# v1.net
KiCad netlist of a schematic drawn in EAGLE
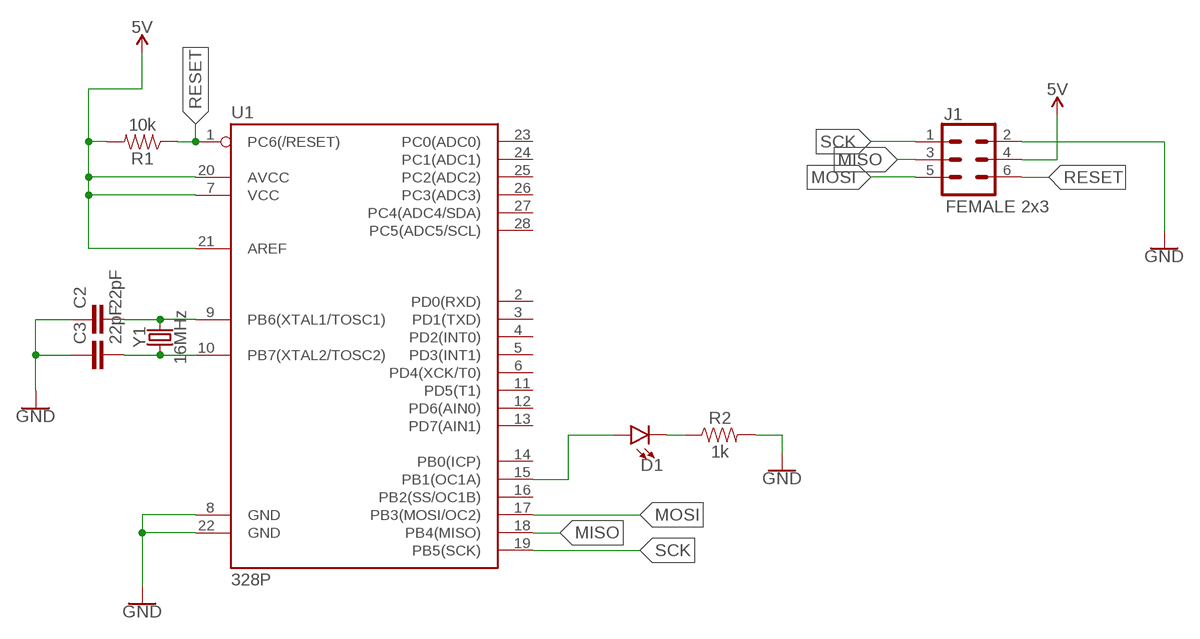
[diagram p0: schematic, sheet 1]

(export (version "E")
  (design (tool "Eeschema 10.0.6"))
  (components
    (comp (ref "C2")
      (value "22pF")
      (footprint "eagle-import:CAP-PTH-2.54")
      (libsource (lib "eagle-import") (part "22PF-PTH-2.54MM-200V-5%"))
    )
    (comp (ref "C3")
      (value "22pF")
      (footprint "eagle-import:CAP-PTH-2.54")
      (libsource (lib "eagle-import") (part "22PF-PTH-2.54MM-200V-5%"))
    )
    (comp (ref "D1")
      (value "LED3MM")
      (footprint "eagle-import:LED_3MM")
      (libsource (lib "eagle-import") (part "LED3MM"))
    )
    (comp (ref "J1")
      (value "FEMALE 2x3")
      (footprint "eagle-import:2X3")
      (libsource (lib "eagle-import") (part "CONN_03X2FEMALE"))
    )
    (comp (ref "R1")
      (value "10k")
      (footprint "eagle-import:AXIAL-0.3")
      (libsource (lib "eagle-import") (part "1KOHM-HORIZ-1/4W-1%"))
    )
    (comp (ref "R2")
      (value "1k")
      (footprint "eagle-import:AXIAL-0.3")
      (libsource (lib "eagle-import") (part "1KOHM-HORIZ-1/4W-1%"))
    )
    (comp (ref "U1")
      (value "328P")
      (footprint "eagle-import:DIP28")
      (libsource (lib "eagle-import") (part "ATMEGA328P_PDIP"))
    )
    (comp (ref "Y1")
      (value "16MHz")
      (footprint "eagle-import:HC49US")
      (libsource (lib "eagle-import") (part "CRYSTAL-16MHZPTH-HC49US"))
    )
  )
  (nets
    (net (code "1") (name "5V") (class "Default")
      (node (ref "J1") (pin "4") (pinfunction "4_4") (pintype "bidirectional"))
      (node (ref "R1") (pin "P$2") (pinfunction "2_P$2") (pintype "passive"))
      (node (ref "U1") (pin "20") (pinfunction "AVCC_20") (pintype "bidirectional"))
      (node (ref "U1") (pin "21") (pinfunction "AREF_21") (pintype "bidirectional"))
      (node (ref "U1") (pin "7") (pinfunction "VCC_7") (pintype "bidirectional"))
    )
    (net (code "2") (name "GND") (class "Default")
      (node (ref "C2") (pin "1") (pinfunction "1_1") (pintype "passive"))
      (node (ref "C3") (pin "1") (pinfunction "1_1") (pintype "passive"))
      (node (ref "J1") (pin "2") (pinfunction "2_2") (pintype "bidirectional"))
      (node (ref "R2") (pin "P$2") (pinfunction "2_P$2") (pintype "passive"))
      (node (ref "U1") (pin "22") (pinfunction "GND_22") (pintype "bidirectional"))
      (node (ref "U1") (pin "8") (pinfunction "GND_8") (pintype "bidirectional"))
    )
    (net (code "3") (name "MISO") (class "Default")
      (node (ref "J1") (pin "3") (pinfunction "3_3") (pintype "bidirectional"))
      (node (ref "U1") (pin "18") (pinfunction "PB4(MISO)_18") (pintype "bidirectional"))
    )
    (net (code "4") (name "MOSI") (class "Default")
      (node (ref "J1") (pin "5") (pinfunction "5_5") (pintype "bidirectional"))
      (node (ref "U1") (pin "17") (pinfunction "PB3(MOSI/OC2)_17") (pintype "bidirectional"))
    )
    (net (code "5") (name "Net-(D1-C)") (class "Default")
      (node (ref "D1") (pin "K") (pinfunction "C_K") (pintype "passive"))
      (node (ref "R2") (pin "P$1") (pinfunction "1_P$1") (pintype "passive"))
    )
    (net (code "6") (name "Net-(U1-PB1(OC1A))") (class "Default")
      (node (ref "D1") (pin "A") (pinfunction "A_A") (pintype "passive"))
      (node (ref "U1") (pin "15") (pinfunction "PB1(OC1A)_15") (pintype "bidirectional"))
    )
    (net (code "7") (name "Net-(U1-PB6(XTAL1{slash}TOSC1))") (class "Default")
      (node (ref "C2") (pin "2") (pinfunction "2_2") (pintype "passive"))
      (node (ref "U1") (pin "9") (pinfunction "PB6(XTAL1/TOSC1)_9") (pintype "bidirectional"))
      (node (ref "Y1") (pin "2") (pinfunction "2_2") (pintype "passive"))
    )
    (net (code "8") (name "Net-(U1-PB7(XTAL2{slash}TOSC2))") (class "Default")
      (node (ref "C3") (pin "2") (pinfunction "2_2") (pintype "passive"))
      (node (ref "U1") (pin "10") (pinfunction "PB7(XTAL2/TOSC2)_10") (pintype "bidirectional"))
      (node (ref "Y1") (pin "1") (pinfunction "1_1") (pintype "passive"))
    )
    (net (code "9") (name "RESET") (class "Default")
      (node (ref "J1") (pin "6") (pinfunction "6_6") (pintype "bidirectional"))
      (node (ref "R1") (pin "P$1") (pinfunction "1_P$1") (pintype "passive"))
      (node (ref "U1") (pin "1") (pinfunction "PC6(/RESET)_1") (pintype "bidirectional"))
    )
    (net (code "10") (name "SCK") (class "Default")
      (node (ref "J1") (pin "1") (pinfunction "1_1") (pintype "bidirectional"))
      (node (ref "U1") (pin "19") (pinfunction "PB5(SCK)_19") (pintype "bidirectional"))
    )
    (net (code "11") (name "unconnected-(U1-PB0(ICP)-Pad14)") (class "Default")
      (node (ref "U1") (pin "14") (pinfunction "PB0(ICP)_14") (pintype "bidirectional"))
    )
    (net (code "12") (name "unconnected-(U1-PB2(SS{slash}OC1B)-Pad16)") (class "Default")
      (node (ref "U1") (pin "16") (pinfunction "PB2(SS/OC1B)_16") (pintype "bidirectional"))
    )
    (net (code "13") (name "unconnected-(U1-PC0(ADC0)-Pad23)") (class "Default")
      (node (ref "U1") (pin "23") (pinfunction "PC0(ADC0)_23") (pintype "bidirectional"))
    )
    (net (code "14") (name "unconnected-(U1-PC1(ADC1)-Pad24)") (class "Default")
      (node (ref "U1") (pin "24") (pinfunction "PC1(ADC1)_24") (pintype "bidirectional"))
    )
    (net (code "15") (name "unconnected-(U1-PC2(ADC2)-Pad25)") (class "Default")
      (node (ref "U1") (pin "25") (pinfunction "PC2(ADC2)_25") (pintype "bidirectional"))
    )
    (net (code "16") (name "unconnected-(U1-PC3(ADC3)-Pad26)") (class "Default")
      (node (ref "U1") (pin "26") (pinfunction "PC3(ADC3)_26") (pintype "bidirectional"))
    )
    (net (code "17") (name "unconnected-(U1-PC4(ADC4{slash}SDA)-Pad27)") (class "Default")
      (node (ref "U1") (pin "27") (pinfunction "PC4(ADC4/SDA)_27") (pintype "bidirectional"))
    )
    (net (code "18") (name "unconnected-(U1-PC5(ADC5{slash}SCL)-Pad28)") (class "Default")
      (node (ref "U1") (pin "28") (pinfunction "PC5(ADC5/SCL)_28") (pintype "bidirectional"))
    )
    (net (code "19") (name "unconnected-(U1-PD0(RXD)-Pad2)") (class "Default")
      (node (ref "U1") (pin "2") (pinfunction "PD0(RXD)_2") (pintype "bidirectional"))
    )
    (net (code "20") (name "unconnected-(U1-PD1(TXD)-Pad3)") (class "Default")
      (node (ref "U1") (pin "3") (pinfunction "PD1(TXD)_3") (pintype "bidirectional"))
    )
    (net (code "21") (name "unconnected-(U1-PD2(INT0)-Pad4)") (class "Default")
      (node (ref "U1") (pin "4") (pinfunction "PD2(INT0)_4") (pintype "bidirectional"))
    )
    (net (code "22") (name "unconnected-(U1-PD3(INT1)-Pad5)") (class "Default")
      (node (ref "U1") (pin "5") (pinfunction "PD3(INT1)_5") (pintype "bidirectional"))
    )
    (net (code "23") (name "unconnected-(U1-PD4(XCK{slash}T0)-Pad6)") (class "Default")
      (node (ref "U1") (pin "6") (pinfunction "PD4(XCK/T0)_6") (pintype "bidirectional"))
    )
    (net (code "24") (name "unconnected-(U1-PD5(T1)-Pad11)") (class "Default")
      (node (ref "U1") (pin "11") (pinfunction "PD5(T1)_11") (pintype "bidirectional"))
    )
    (net (code "25") (name "unconnected-(U1-PD6(AIN0)-Pad12)") (class "Default")
      (node (ref "U1") (pin "12") (pinfunction "PD6(AIN0)_12") (pintype "bidirectional"))
    )
    (net (code "26") (name "unconnected-(U1-PD7(AIN1)-Pad13)") (class "Default")
      (node (ref "U1") (pin "13") (pinfunction "PD7(AIN1)_13") (pintype "bidirectional"))
    )
  )
)
